# Current_sensing.net
KiCad netlist of a schematic drawn in Altium Designer
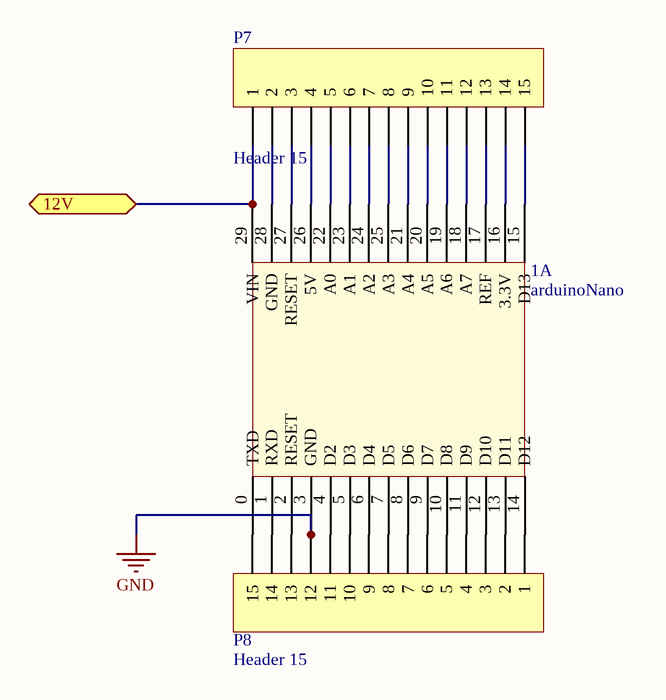
[diagram p0: Current sensing.SchDoc]

(export (version "E")
  (design (tool "Eeschema 10.0.6"))
  (components
    (comp (ref "1A")
      (value "arduinoNano")
      (footprint "Arduino nano")
      (libsource (lib "Arduino Nano") (part "arduinoNano"))
    )
    (comp (ref "P7")
      (value "Header 15")
      (footprint "HDR1X15")
      (description "Header, 15-Pin")
      (fields (field (name "PUBLISHER") "Altium Limited"))
      (libsource (lib "") (part "Header 15_1"))
    )
    (comp (ref "P8")
      (value "Header 15")
      (footprint "HDR1X15")
      (description "Header, 15-Pin")
      (fields (field (name "PUBLISHER") "Altium Limited"))
      (libsource (lib "Miscellaneous Connectors") (part "Header 15"))
    )
  )
  (nets
    (net (code "1") (name "/12V") (class "Default")
      (node (ref "1A") (pin "29") (pinfunction "VIN_29") (pintype "passive"))
      (node (ref "P7") (pin "1") (pinfunction "1_1") (pintype "passive"))
    )
    (net (code "2") (name "GND") (class "Default")
      (node (ref "1A") (pin "3") (pinfunction "GND_3") (pintype "passive"))
      (node (ref "P8") (pin "12") (pinfunction "12_12") (pintype "passive"))
    )
    (net (code "3") (name "Net-(1A-3.3V)") (class "Default")
      (node (ref "1A") (pin "16") (pinfunction "3.3V_16") (pintype "passive"))
      (node (ref "P7") (pin "14") (pinfunction "14_14") (pintype "passive"))
    )
    (net (code "4") (name "Net-(1A-5V)") (class "Default")
      (node (ref "1A") (pin "26") (pinfunction "5V_26") (pintype "passive"))
      (node (ref "P7") (pin "4") (pinfunction "4_4") (pintype "passive"))
    )
    (net (code "5") (name "Net-(1A-A0)") (class "Default")
      (node (ref "1A") (pin "22") (pinfunction "A0_22") (pintype "passive"))
      (node (ref "P7") (pin "5") (pinfunction "5_5") (pintype "passive"))
    )
    (net (code "6") (name "Net-(1A-A1)") (class "Default")
      (node (ref "1A") (pin "23") (pinfunction "A1_23") (pintype "passive"))
      (node (ref "P7") (pin "6") (pinfunction "6_6") (pintype "passive"))
    )
    (net (code "7") (name "Net-(1A-A2)") (class "Default")
      (node (ref "1A") (pin "24") (pinfunction "A2_24") (pintype "passive"))
      (node (ref "P7") (pin "7") (pinfunction "7_7") (pintype "passive"))
    )
    (net (code "8") (name "Net-(1A-A3)") (class "Default")
      (node (ref "1A") (pin "25") (pinfunction "A3_25") (pintype "passive"))
      (node (ref "P7") (pin "8") (pinfunction "8_8") (pintype "passive"))
    )
    (net (code "9") (name "Net-(1A-A4)") (class "Default")
      (node (ref "1A") (pin "21") (pinfunction "A4_21") (pintype "passive"))
      (node (ref "P7") (pin "9") (pinfunction "9_9") (pintype "passive"))
    )
    (net (code "10") (name "Net-(1A-A5)") (class "Default")
      (node (ref "1A") (pin "20") (pinfunction "A5_20") (pintype "passive"))
      (node (ref "P7") (pin "10") (pinfunction "10_10") (pintype "passive"))
    )
    (net (code "11") (name "Net-(1A-A6)") (class "Default")
      (node (ref "1A") (pin "19") (pinfunction "A6_19") (pintype "passive"))
      (node (ref "P7") (pin "11") (pinfunction "11_11") (pintype "passive"))
    )
    (net (code "12") (name "Net-(1A-A7)") (class "Default")
      (node (ref "1A") (pin "18") (pinfunction "A7_18") (pintype "passive"))
      (node (ref "P7") (pin "12") (pinfunction "12_12") (pintype "passive"))
    )
    (net (code "13") (name "Net-(1A-D2)") (class "Default")
      (node (ref "1A") (pin "4") (pinfunction "D2_4") (pintype "passive"))
      (node (ref "P8") (pin "11") (pinfunction "11_11") (pintype "passive"))
    )
    (net (code "14") (name "Net-(1A-D3)") (class "Default")
      (node (ref "1A") (pin "5") (pinfunction "D3_5") (pintype "passive"))
      (node (ref "P8") (pin "10") (pinfunction "10_10") (pintype "passive"))
    )
    (net (code "15") (name "Net-(1A-D4)") (class "Default")
      (node (ref "1A") (pin "6") (pinfunction "D4_6") (pintype "passive"))
      (node (ref "P8") (pin "9") (pinfunction "9_9") (pintype "passive"))
    )
    (net (code "16") (name "Net-(1A-D5)") (class "Default")
      (node (ref "1A") (pin "7") (pinfunction "D5_7") (pintype "passive"))
      (node (ref "P8") (pin "8") (pinfunction "8_8") (pintype "passive"))
    )
    (net (code "17") (name "Net-(1A-D6)") (class "Default")
      (node (ref "1A") (pin "8") (pinfunction "D6_8") (pintype "passive"))
      (node (ref "P8") (pin "7") (pinfunction "7_7") (pintype "passive"))
    )
    (net (code "18") (name "Net-(1A-D7)") (class "Default")
      (node (ref "1A") (pin "9") (pinfunction "D7_9") (pintype "passive"))
      (node (ref "P8") (pin "6") (pinfunction "6_6") (pintype "passive"))
    )
    (net (code "19") (name "Net-(1A-D8)") (class "Default")
      (node (ref "1A") (pin "10") (pinfunction "D8_10") (pintype "passive"))
      (node (ref "P8") (pin "5") (pinfunction "5_5") (pintype "passive"))
    )
    (net (code "20") (name "Net-(1A-D9)") (class "Default")
      (node (ref "1A") (pin "11") (pinfunction "D9_11") (pintype "passive"))
      (node (ref "P8") (pin "4") (pinfunction "4_4") (pintype "passive"))
    )
    (net (code "21") (name "Net-(1A-D10)") (class "Default")
      (node (ref "1A") (pin "12") (pinfunction "D10_12") (pintype "passive"))
      (node (ref "P8") (pin "3") (pinfunction "3_3") (pintype "passive"))
    )
    (net (code "22") (name "Net-(1A-D11)") (class "Default")
      (node (ref "1A") (pin "13") (pinfunction "D11_13") (pintype "passive"))
      (node (ref "P8") (pin "2") (pinfunction "2_2") (pintype "passive"))
    )
    (net (code "23") (name "Net-(1A-D12)") (class "Default")
      (node (ref "1A") (pin "14") (pinfunction "D12_14") (pintype "passive"))
      (node (ref "P8") (pin "1") (pinfunction "1_1") (pintype "passive"))
    )
    (net (code "24") (name "Net-(1A-D13)") (class "Default")
      (node (ref "1A") (pin "15") (pinfunction "D13_15") (pintype "passive"))
      (node (ref "P7") (pin "15") (pinfunction "15_15") (pintype "passive"))
    )
    (net (code "25") (name "Net-(1A-GND-Pad28)") (class "Default")
      (node (ref "1A") (pin "28") (pinfunction "GND_28") (pintype "passive"))
      (node (ref "P7") (pin "2") (pinfunction "2_2") (pintype "passive"))
    )
    (net (code "26") (name "Net-(1A-REF)") (class "Default")
      (node (ref "1A") (pin "17") (pinfunction "REF_17") (pintype "passive"))
      (node (ref "P7") (pin "13") (pinfunction "13_13") (pintype "passive"))
    )
    (net (code "27") (name "Net-(1A-RESET-Pad2)") (class "Default")
      (node (ref "1A") (pin "2") (pinfunction "RESET_2") (pintype "passive"))
      (node (ref "P8") (pin "13") (pinfunction "13_13") (pintype "passive"))
    )
    (net (code "28") (name "Net-(1A-RESET-Pad27)") (class "Default")
      (node (ref "1A") (pin "27") (pinfunction "RESET_27") (pintype "passive"))
      (node (ref "P7") (pin "3") (pinfunction "3_3") (pintype "passive"))
    )
    (net (code "29") (name "Net-(1A-RXD)") (class "Default")
      (node (ref "1A") (pin "1") (pinfunction "RXD_1") (pintype "passive"))
      (node (ref "P8") (pin "14") (pinfunction "14_14") (pintype "passive"))
    )
    (net (code "30") (name "Net-(1A-TXD)") (class "Default")
      (node (ref "1A") (pin "0") (pinfunction "TXD_0") (pintype "passive"))
      (node (ref "P8") (pin "15") (pinfunction "15_15") (pintype "passive"))
    )
  )
)
